# EstacionMetro.net
KiCad netlist of a schematic drawn in EAGLE
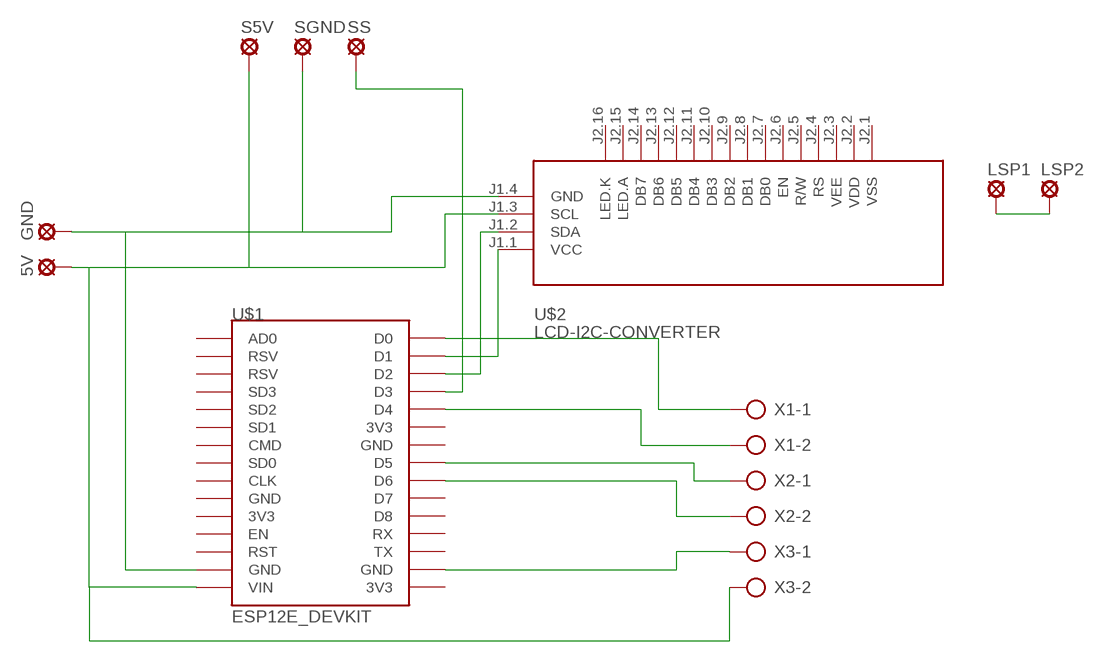
[diagram p0: schematic, sheet 1]

(export (version "E")
  (design (tool "Eeschema 10.0.6"))
  (components
    (comp (ref "5V")
      (value "SE11")
      (footprint "eagle-import:SE11")
      (libsource (lib "eagle-import") (part "SE11"))
    )
    (comp (ref "GND")
      (value "SE11")
      (footprint "eagle-import:SE11")
      (libsource (lib "eagle-import") (part "SE11"))
    )
    (comp (ref "LSP1")
      (value "SE11")
      (footprint "eagle-import:SE11")
      (libsource (lib "eagle-import") (part "SE11"))
    )
    (comp (ref "LSP2")
      (value "SE11")
      (footprint "eagle-import:SE11")
      (libsource (lib "eagle-import") (part "SE11"))
    )
    (comp (ref "S5V")
      (value "SE11")
      (footprint "eagle-import:SE11")
      (libsource (lib "eagle-import") (part "SE11"))
    )
    (comp (ref "SGND")
      (value "SE11")
      (footprint "eagle-import:SE11")
      (libsource (lib "eagle-import") (part "SE11"))
    )
    (comp (ref "SS")
      (value "SE11")
      (footprint "eagle-import:SE11")
      (libsource (lib "eagle-import") (part "SE11"))
    )
    (comp (ref "U$1")
      (value "ESP12E_DEVKIT")
      (footprint "eagle-import:ESP12E_DEVKIT")
      (libsource (lib "eagle-import") (part "ESP12E_DEVKIT"))
    )
    (comp (ref "U$2")
      (value "LCD-I2C-CONVERTER")
      (footprint "eagle-import:LCD-I2C-CONVERTER")
      (libsource (lib "eagle-import") (part "LCD-I2C-CONVERTER"))
    )
    (comp (ref "X1")
      (value "AK500/2")
      (footprint "eagle-import:AK500_2")
      (libsource (lib "eagle-import") (part "AK500/2"))
    )
    (comp (ref "X2")
      (value "AK500/2")
      (footprint "eagle-import:AK500_2")
      (libsource (lib "eagle-import") (part "AK500/2"))
    )
    (comp (ref "X3")
      (value "AK500/2")
      (footprint "eagle-import:AK500_2")
      (libsource (lib "eagle-import") (part "AK500/2"))
    )
  )
  (nets
    (net (code "1") (name "Net-(LSP1-PadMP)") (class "Default")
      (node (ref "LSP1") (pin "MP") (pinfunction "MP_MP") (pintype "passive"))
      (node (ref "LSP2") (pin "MP") (pinfunction "MP_MP") (pintype "passive"))
    )
    (net (code "2") (name "Net-(SS-PadMP)") (class "Default")
      (node (ref "SS") (pin "MP") (pinfunction "MP_MP") (pintype "passive"))
      (node (ref "U$1") (pin "D3") (pinfunction "D3_D3") (pintype "bidirectional"))
    )
    (net (code "3") (name "Net-(U$2-GND)") (class "Default")
      (node (ref "GND") (pin "MP") (pinfunction "MP_MP") (pintype "passive"))
      (node (ref "SGND") (pin "MP") (pinfunction "MP_MP") (pintype "passive"))
      (node (ref "U$1") (pin "GND@1") (pinfunction "GND_GND@1") (pintype "bidirectional"))
      (node (ref "U$2") (pin "J1.4") (pinfunction "GND_J1.4") (pintype "power_in"))
    )
    (net (code "4") (name "Net-(U$2-SCL)") (class "Default")
      (node (ref "5V") (pin "MP") (pinfunction "MP_MP") (pintype "passive"))
      (node (ref "S5V") (pin "MP") (pinfunction "MP_MP") (pintype "passive"))
      (node (ref "U$1") (pin "VIN") (pinfunction "VIN_VIN") (pintype "bidirectional"))
      (node (ref "U$2") (pin "J1.3") (pinfunction "SCL_J1.3") (pintype "bidirectional"))
      (node (ref "X3") (pin "2") (pinfunction "KL_2") (pintype "passive"))
    )
    (net (code "5") (name "Net-(U$2-SDA)") (class "Default")
      (node (ref "U$1") (pin "D2") (pinfunction "D2_D2") (pintype "bidirectional"))
      (node (ref "U$2") (pin "J1.2") (pinfunction "SDA_J1.2") (pintype "bidirectional"))
    )
    (net (code "6") (name "Net-(U$2-VCC)") (class "Default")
      (node (ref "U$1") (pin "D1") (pinfunction "D1_D1") (pintype "bidirectional"))
      (node (ref "U$2") (pin "J1.1") (pinfunction "VCC_J1.1") (pintype "power_in"))
    )
    (net (code "7") (name "Net-(X1A-KL)") (class "Default")
      (node (ref "U$1") (pin "D0") (pinfunction "D0_D0") (pintype "bidirectional"))
      (node (ref "X1") (pin "1") (pinfunction "KL_1") (pintype "passive"))
    )
    (net (code "8") (name "Net-(X1B-KL)") (class "Default")
      (node (ref "U$1") (pin "D4") (pinfunction "D4_D4") (pintype "bidirectional"))
      (node (ref "X1") (pin "2") (pinfunction "KL_2") (pintype "passive"))
    )
    (net (code "9") (name "Net-(X2A-KL)") (class "Default")
      (node (ref "U$1") (pin "D5") (pinfunction "D5_D5") (pintype "bidirectional"))
      (node (ref "X2") (pin "1") (pinfunction "KL_1") (pintype "passive"))
    )
    (net (code "10") (name "Net-(X2B-KL)") (class "Default")
      (node (ref "U$1") (pin "D6") (pinfunction "D6_D6") (pintype "bidirectional"))
      (node (ref "X2") (pin "2") (pinfunction "KL_2") (pintype "passive"))
    )
    (net (code "11") (name "Net-(X3A-KL)") (class "Default")
      (node (ref "U$1") (pin "GND@3") (pinfunction "GND_GND@3") (pintype "bidirectional"))
      (node (ref "X3") (pin "1") (pinfunction "KL_1") (pintype "passive"))
    )
    (net (code "12") (name "unconnected-(U$1-3V3-Pad3V3@0)") (class "Default")
      (node (ref "U$1") (pin "3V3@0") (pinfunction "3V3_3V3@0") (pintype "bidirectional"))
    )
    (net (code "13") (name "unconnected-(U$1-3V3-Pad3V3@1)") (class "Default")
      (node (ref "U$1") (pin "3V3@1") (pinfunction "3V3_3V3@1") (pintype "bidirectional"))
    )
    (net (code "14") (name "unconnected-(U$1-3V3-Pad3V3@2)") (class "Default")
      (node (ref "U$1") (pin "3V3@2") (pinfunction "3V3_3V3@2") (pintype "bidirectional"))
    )
    (net (code "15") (name "unconnected-(U$1-GND-PadGND@0)") (class "Default")
      (node (ref "U$1") (pin "GND@0") (pinfunction "GND_GND@0") (pintype "bidirectional"))
    )
    (net (code "16") (name "unconnected-(U$1-GND-PadGND@2)") (class "Default")
      (node (ref "U$1") (pin "GND@2") (pinfunction "GND_GND@2") (pintype "bidirectional"))
    )
    (net (code "17") (name "unconnected-(U$1-PadAD0)") (class "Default")
      (node (ref "U$1") (pin "AD0") (pinfunction "AD0_AD0") (pintype "bidirectional"))
    )
    (net (code "18") (name "unconnected-(U$1-PadCLK)") (class "Default")
      (node (ref "U$1") (pin "CLK") (pinfunction "CLK_CLK") (pintype "bidirectional"))
    )
    (net (code "19") (name "unconnected-(U$1-PadCMD)") (class "Default")
      (node (ref "U$1") (pin "CMD") (pinfunction "CMD_CMD") (pintype "bidirectional"))
    )
    (net (code "20") (name "unconnected-(U$1-PadD7)") (class "Default")
      (node (ref "U$1") (pin "D7") (pinfunction "D7_D7") (pintype "bidirectional"))
    )
    (net (code "21") (name "unconnected-(U$1-PadD8)") (class "Default")
      (node (ref "U$1") (pin "D8") (pinfunction "D8_D8") (pintype "bidirectional"))
    )
    (net (code "22") (name "unconnected-(U$1-PadEN)") (class "Default")
      (node (ref "U$1") (pin "EN") (pinfunction "EN_EN") (pintype "bidirectional"))
    )
    (net (code "23") (name "unconnected-(U$1-PadRST)") (class "Default")
      (node (ref "U$1") (pin "RST") (pinfunction "RST_RST") (pintype "bidirectional"))
    )
    (net (code "24") (name "unconnected-(U$1-PadRX)") (class "Default")
      (node (ref "U$1") (pin "RX") (pinfunction "RX_RX") (pintype "bidirectional"))
    )
    (net (code "25") (name "unconnected-(U$1-PadSD0)") (class "Default")
      (node (ref "U$1") (pin "SD0") (pinfunction "SD0_SD0") (pintype "bidirectional"))
    )
    (net (code "26") (name "unconnected-(U$1-PadSD1)") (class "Default")
      (node (ref "U$1") (pin "SD1") (pinfunction "SD1_SD1") (pintype "bidirectional"))
    )
    (net (code "27") (name "unconnected-(U$1-PadSD2)") (class "Default")
      (node (ref "U$1") (pin "SD2") (pinfunction "SD2_SD2") (pintype "bidirectional"))
    )
    (net (code "28") (name "unconnected-(U$1-PadSD3)") (class "Default")
      (node (ref "U$1") (pin "SD3") (pinfunction "SD3_SD3") (pintype "bidirectional"))
    )
    (net (code "29") (name "unconnected-(U$1-PadTX)") (class "Default")
      (node (ref "U$1") (pin "TX") (pinfunction "TX_TX") (pintype "bidirectional"))
    )
    (net (code "30") (name "unconnected-(U$1-RSV-PadRSV@0)") (class "Default")
      (node (ref "U$1") (pin "RSV@0") (pinfunction "RSV_RSV@0") (pintype "bidirectional"))
    )
    (net (code "31") (name "unconnected-(U$1-RSV-PadRSV@1)") (class "Default")
      (node (ref "U$1") (pin "RSV@1") (pinfunction "RSV_RSV@1") (pintype "bidirectional"))
    )
    (net (code "32") (name "unconnected-(U$2-DB0-PadJ2.7)") (class "Default")
      (node (ref "U$2") (pin "J2.7") (pinfunction "DB0_J2.7") (pintype "bidirectional"))
    )
    (net (code "33") (name "unconnected-(U$2-DB1-PadJ2.8)") (class "Default")
      (node (ref "U$2") (pin "J2.8") (pinfunction "DB1_J2.8") (pintype "bidirectional"))
    )
    (net (code "34") (name "unconnected-(U$2-DB2-PadJ2.9)") (class "Default")
      (node (ref "U$2") (pin "J2.9") (pinfunction "DB2_J2.9") (pintype "bidirectional"))
    )
    (net (code "35") (name "unconnected-(U$2-DB3-PadJ2.10)") (class "Default")
      (node (ref "U$2") (pin "J2.10") (pinfunction "DB3_J2.10") (pintype "bidirectional"))
    )
    (net (code "36") (name "unconnected-(U$2-DB4-PadJ2.11)") (class "Default")
      (node (ref "U$2") (pin "J2.11") (pinfunction "DB4_J2.11") (pintype "bidirectional"))
    )
    (net (code "37") (name "unconnected-(U$2-DB5-PadJ2.12)") (class "Default")
      (node (ref "U$2") (pin "J2.12") (pinfunction "DB5_J2.12") (pintype "bidirectional"))
    )
    (net (code "38") (name "unconnected-(U$2-DB6-PadJ2.13)") (class "Default")
      (node (ref "U$2") (pin "J2.13") (pinfunction "DB6_J2.13") (pintype "bidirectional"))
    )
    (net (code "39") (name "unconnected-(U$2-DB7-PadJ2.14)") (class "Default")
      (node (ref "U$2") (pin "J2.14") (pinfunction "DB7_J2.14") (pintype "bidirectional"))
    )
    (net (code "40") (name "unconnected-(U$2-EN-PadJ2.6)") (class "Default")
      (node (ref "U$2") (pin "J2.6") (pinfunction "EN_J2.6") (pintype "bidirectional"))
    )
    (net (code "41") (name "unconnected-(U$2-LED.A-PadJ2.15)") (class "Default")
      (node (ref "U$2") (pin "J2.15") (pinfunction "LED.A_J2.15") (pintype "bidirectional"))
    )
    (net (code "42") (name "unconnected-(U$2-LED.K-PadJ2.16)") (class "Default")
      (node (ref "U$2") (pin "J2.16") (pinfunction "LED.K_J2.16") (pintype "bidirectional"))
    )
    (net (code "43") (name "unconnected-(U$2-RS-PadJ2.4)") (class "Default")
      (node (ref "U$2") (pin "J2.4") (pinfunction "RS_J2.4") (pintype "bidirectional"))
    )
    (net (code "44") (name "unconnected-(U$2-R{slash}W-PadJ2.5)") (class "Default")
      (node (ref "U$2") (pin "J2.5") (pinfunction "R/W_J2.5") (pintype "bidirectional"))
    )
    (net (code "45") (name "unconnected-(U$2-VDD-PadJ2.2)") (class "Default")
      (node (ref "U$2") (pin "J2.2") (pinfunction "VDD_J2.2") (pintype "bidirectional"))
    )
    (net (code "46") (name "unconnected-(U$2-VEE-PadJ2.3)") (class "Default")
      (node (ref "U$2") (pin "J2.3") (pinfunction "VEE_J2.3") (pintype "bidirectional"))
    )
    (net (code "47") (name "unconnected-(U$2-VSS-PadJ2.1)") (class "Default")
      (node (ref "U$2") (pin "J2.1") (pinfunction "VSS_J2.1") (pintype "bidirectional"))
    )
  )
)
